# Sheet_MP.net
KiCad netlist of a schematic drawn in Altium Designer
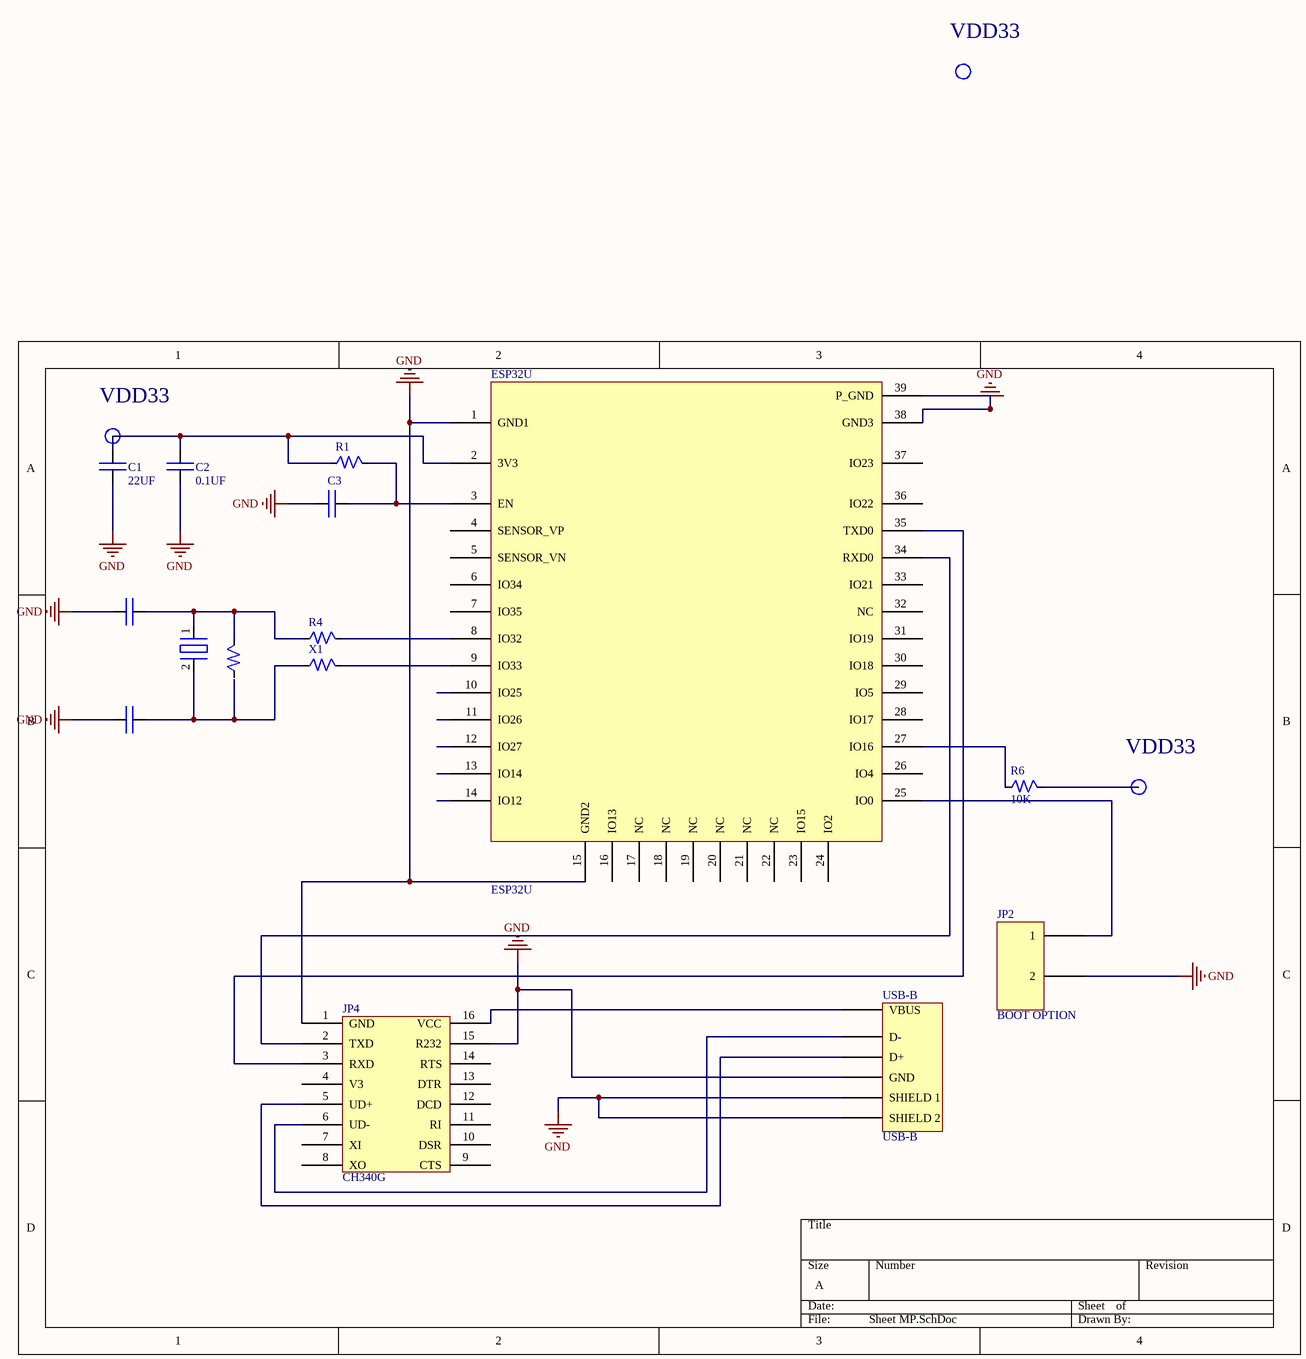
[diagram p0: Sheet MP.SchDoc]

(export (version "E")
  (design (tool "Eeschema 10.0.6"))
  (components
    (comp (ref "C1")
      (value "22UF")
      (footprint "Capacitor")
      (fields (field (name "MANUFACTURER") "PANASONIC") (field (name "MANUFACTURER PART") "EEHZA1V470P"))
      (libsource (lib "SchlibMP") (part "CAP"))
    )
    (comp (ref "C2")
      (value "0.1UF")
      (footprint "Capacitor")
      (fields (field (name "MANUFACTURER") "PANASONIC") (field (name "MANUFACTURER PART") "EEHZA1V470P"))
      (libsource (lib "SchlibMP") (part "CAP"))
    )
    (comp (ref "C3")
      (value "CAP")
      (footprint "Capacitor")
      (fields (field (name "MANUFACTURER") "PANASONIC") (field (name "MANUFACTURER PART") "EEHZA1V470P"))
      (libsource (lib "SchlibMP") (part "CAP"))
    )
    (comp (ref "C4")
      (value "CAP")
      (footprint "Capacitor")
      (fields (field (name "MANUFACTURER") "PANASONIC") (field (name "MANUFACTURER PART") "EEHZA1V470P"))
      (libsource (lib "SchlibMP") (part "CAP"))
    )
    (comp (ref "C5")
      (value "CAP")
      (footprint "Capacitor")
      (fields (field (name "MANUFACTURER") "PANASONIC") (field (name "MANUFACTURER PART") "EEHZA1V470P"))
      (libsource (lib "SchlibMP") (part "CAP"))
    )
    (comp (ref "ESP32U")
      (value "ESP32U")
      (footprint "ESP32U")
      (fields (field (name "MANUFACTURER") "Ai-Thinker") (field (name "MANUFACTURER PART") "ESP32-S"))
      (libsource (lib "SchlibMP") (part "ESP32U"))
    )
    (comp (ref "JP2")
      (value "BOOT OPTION")
      (footprint "HEADER 2 PINS - duplicate")
      (fields
        (field (name "MANUFACTURER") "JST Sales America Inc.")
        (field (name "MANUFACTURER PART") "B2B-XH-A")
      )
      (libsource (lib "SchlibMP") (part "HEADER 2 PINS"))
    )
    (comp (ref "JP4")
      (value "CH340G")
      (footprint "CH340G - duplicate1")
      (fields (field (name "MANUFACTURER") "WCH"))
      (libsource (lib "SchlibMP") (part "CH340G"))
    )
    (comp (ref "R1")
      (value "0805")
      (footprint "Resistor")
      (fields (field (name "MANUFACTURER") "YAGEO") (field (name "MANUFACTURER PART") "RC0805FR-0710KL"))
      (libsource (lib "SchlibMP") (part "0805"))
    )
    (comp (ref "R4")
      (value "0805")
      (footprint "Resistor")
      (fields (field (name "MANUFACTURER") "YAGEO") (field (name "MANUFACTURER PART") "RC0805FR-0710KL"))
      (libsource (lib "SchlibMP") (part "0805"))
    )
    (comp (ref "R5")
      (value "0805")
      (footprint "Resistor")
      (fields (field (name "MANUFACTURER") "YAGEO") (field (name "MANUFACTURER PART") "RC0805FR-0710KL"))
      (libsource (lib "SchlibMP") (part "0805"))
    )
    (comp (ref "R6")
      (value "10K")
      (footprint "Resistor")
      (fields (field (name "MANUFACTURER") "YAGEO") (field (name "MANUFACTURER PART") "RC0805FR-0710KL"))
      (libsource (lib "SchlibMP") (part "0805"))
    )
    (comp (ref "T1")
      (value "CRYSTAL")
      (footprint "CRYSTAL")
      (fields (field (name "MANUFACTURER") "EPSON") (field (name "MANUFACTURER PART") "Q13FC13500004"))
      (libsource (lib "SchlibMP") (part "CRYSTAL"))
    )
    (comp (ref "USB-B")
      (value "USB-B")
      (footprint "USB-B - duplicate1")
      (fields (field (name "MANUFACTURER") "Switchcraft Inc.") (field (name "MANUFACTURER PART") "RAHUB20"))
      (libsource (lib "SchlibMP") (part "USB-B"))
    )
    (comp (ref "X1")
      (value "0805")
      (footprint "Resistor")
      (fields (field (name "MANUFACTURER") "YAGEO") (field (name "MANUFACTURER PART") "RC0805FR-0710KL"))
      (libsource (lib "SchlibMP") (part "0805"))
    )
  )
  (nets
    (net (code "1") (name "GND") (class "Default")
      (node (ref "C1") (pin "1") (pinfunction "1_1") (pintype "passive"))
      (node (ref "C2") (pin "1") (pinfunction "1_1") (pintype "passive"))
      (node (ref "C3") (pin "2") (pinfunction "2_2") (pintype "passive"))
      (node (ref "C4") (pin "2") (pinfunction "2_2") (pintype "passive"))
      (node (ref "C5") (pin "2") (pinfunction "2_2") (pintype "passive"))
      (node (ref "ESP32U") (pin "1") (pinfunction "GND1_1") (pintype "passive"))
      (node (ref "ESP32U") (pin "15") (pinfunction "GND2_15") (pintype "passive"))
      (node (ref "ESP32U") (pin "38") (pinfunction "GND3_38") (pintype "passive"))
      (node (ref "ESP32U") (pin "39") (pinfunction "P_GND_39") (pintype "passive"))
      (node (ref "JP2") (pin "2") (pinfunction "2_2") (pintype "passive"))
      (node (ref "JP4") (pin "1") (pinfunction "GND_1") (pintype "passive"))
      (node (ref "JP4") (pin "15") (pinfunction "R232_15") (pintype "passive"))
      (node (ref "USB-B") (pin "4") (pinfunction "GND_4") (pintype "passive"))
      (node (ref "USB-B") (pin "5") (pinfunction "SHIELD_1_5") (pintype "passive"))
      (node (ref "USB-B") (pin "6") (pinfunction "SHIELD_2_6") (pintype "passive"))
    )
    (net (code "2") (name "Net-(C4-Pad1)") (class "Default")
      (node (ref "C4") (pin "1") (pinfunction "1_1") (pintype "passive"))
      (node (ref "T1") (pin "2") (pinfunction "2_2") (pintype "passive"))
      (node (ref "X1") (pin "1") (pinfunction "1_1") (pintype "passive"))
    )
    (net (code "3") (name "Net-(C5-Pad1)") (class "Default")
      (node (ref "C5") (pin "1") (pinfunction "1_1") (pintype "passive"))
      (node (ref "R4") (pin "1") (pinfunction "1_1") (pintype "passive"))
      (node (ref "R5") (pin "2") (pinfunction "2_2") (pintype "passive"))
      (node (ref "T1") (pin "1") (pinfunction "1_1") (pintype "passive"))
    )
    (net (code "4") (name "Net-(ESP32U-3V3)") (class "Default")
      (node (ref "C1") (pin "2") (pinfunction "2_2") (pintype "passive"))
      (node (ref "C2") (pin "2") (pinfunction "2_2") (pintype "passive"))
      (node (ref "ESP32U") (pin "2") (pinfunction "3V3_2") (pintype "passive"))
      (node (ref "R1") (pin "1") (pinfunction "1_1") (pintype "passive"))
    )
    (net (code "5") (name "Net-(ESP32U-EN)") (class "Default")
      (node (ref "C3") (pin "1") (pinfunction "1_1") (pintype "passive"))
      (node (ref "ESP32U") (pin "3") (pinfunction "EN_3") (pintype "passive"))
      (node (ref "R1") (pin "2") (pinfunction "2_2") (pintype "passive"))
    )
    (net (code "6") (name "Net-(ESP32U-IO0)") (class "Default")
      (node (ref "ESP32U") (pin "25") (pinfunction "IO0_25") (pintype "passive"))
      (node (ref "JP2") (pin "1") (pinfunction "1_1") (pintype "passive"))
    )
    (net (code "7") (name "Net-(ESP32U-IO16)") (class "Default")
      (node (ref "ESP32U") (pin "27") (pinfunction "IO16_27") (pintype "passive"))
      (node (ref "R6") (pin "1") (pinfunction "1_1") (pintype "passive"))
    )
    (net (code "8") (name "Net-(ESP32U-IO32)") (class "Default")
      (node (ref "ESP32U") (pin "8") (pinfunction "IO32_8") (pintype "passive"))
      (node (ref "R4") (pin "2") (pinfunction "2_2") (pintype "passive"))
    )
    (net (code "9") (name "Net-(ESP32U-IO33)") (class "Default")
      (node (ref "ESP32U") (pin "9") (pinfunction "IO33_9") (pintype "passive"))
      (node (ref "X1") (pin "2") (pinfunction "2_2") (pintype "passive"))
    )
    (net (code "10") (name "Net-(ESP32U-RXD0)") (class "Default")
      (node (ref "ESP32U") (pin "34") (pinfunction "RXD0_34") (pintype "passive"))
      (node (ref "JP4") (pin "2") (pinfunction "TXD_2") (pintype "passive"))
    )
    (net (code "11") (name "Net-(ESP32U-TXD0)") (class "Default")
      (node (ref "ESP32U") (pin "35") (pinfunction "TXD0_35") (pintype "passive"))
      (node (ref "JP4") (pin "3") (pinfunction "RXD_3") (pintype "passive"))
    )
    (net (code "12") (name "Net-(JP4-UD+)") (class "Default")
      (node (ref "JP4") (pin "5") (pinfunction "UD+_5") (pintype "passive"))
      (node (ref "USB-B") (pin "3") (pinfunction "D+_3") (pintype "passive"))
    )
    (net (code "13") (name "Net-(JP4-UD-)") (class "Default")
      (node (ref "JP4") (pin "6") (pinfunction "UD-_6") (pintype "passive"))
      (node (ref "USB-B") (pin "2") (pinfunction "D-_2") (pintype "passive"))
    )
    (net (code "14") (name "Net-(JP4-VCC)") (class "Default")
      (node (ref "JP4") (pin "16") (pinfunction "VCC_16") (pintype "passive"))
      (node (ref "USB-B") (pin "1") (pinfunction "VBUS_1") (pintype "passive"))
    )
    (net (code "15") (name "unconnected-(ESP32U-IO2-Pad24)") (class "Default")
      (node (ref "ESP32U") (pin "24") (pinfunction "IO2_24") (pintype "passive"))
    )
    (net (code "16") (name "unconnected-(ESP32U-IO4-Pad26)") (class "Default")
      (node (ref "ESP32U") (pin "26") (pinfunction "IO4_26") (pintype "passive"))
    )
    (net (code "17") (name "unconnected-(ESP32U-IO5-Pad29)") (class "Default")
      (node (ref "ESP32U") (pin "29") (pinfunction "IO5_29") (pintype "passive"))
    )
    (net (code "18") (name "unconnected-(ESP32U-IO12-Pad14)") (class "Default")
      (node (ref "ESP32U") (pin "14") (pinfunction "IO12_14") (pintype "passive"))
    )
    (net (code "19") (name "unconnected-(ESP32U-IO13-Pad16)") (class "Default")
      (node (ref "ESP32U") (pin "16") (pinfunction "IO13_16") (pintype "passive"))
    )
    (net (code "20") (name "unconnected-(ESP32U-IO14-Pad13)") (class "Default")
      (node (ref "ESP32U") (pin "13") (pinfunction "IO14_13") (pintype "passive"))
    )
    (net (code "21") (name "unconnected-(ESP32U-IO15-Pad23)") (class "Default")
      (node (ref "ESP32U") (pin "23") (pinfunction "IO15_23") (pintype "passive"))
    )
    (net (code "22") (name "unconnected-(ESP32U-IO17-Pad28)") (class "Default")
      (node (ref "ESP32U") (pin "28") (pinfunction "IO17_28") (pintype "passive"))
    )
    (net (code "23") (name "unconnected-(ESP32U-IO18-Pad30)") (class "Default")
      (node (ref "ESP32U") (pin "30") (pinfunction "IO18_30") (pintype "passive"))
    )
    (net (code "24") (name "unconnected-(ESP32U-IO19-Pad31)") (class "Default")
      (node (ref "ESP32U") (pin "31") (pinfunction "IO19_31") (pintype "passive"))
    )
    (net (code "25") (name "unconnected-(ESP32U-IO21-Pad33)") (class "Default")
      (node (ref "ESP32U") (pin "33") (pinfunction "IO21_33") (pintype "passive"))
    )
    (net (code "26") (name "unconnected-(ESP32U-IO22-Pad36)") (class "Default")
      (node (ref "ESP32U") (pin "36") (pinfunction "IO22_36") (pintype "passive"))
    )
    (net (code "27") (name "unconnected-(ESP32U-IO23-Pad37)") (class "Default")
      (node (ref "ESP32U") (pin "37") (pinfunction "IO23_37") (pintype "passive"))
    )
    (net (code "28") (name "unconnected-(ESP32U-IO25-Pad10)") (class "Default")
      (node (ref "ESP32U") (pin "10") (pinfunction "IO25_10") (pintype "passive"))
    )
    (net (code "29") (name "unconnected-(ESP32U-IO26-Pad11)") (class "Default")
      (node (ref "ESP32U") (pin "11") (pinfunction "IO26_11") (pintype "passive"))
    )
    (net (code "30") (name "unconnected-(ESP32U-IO27-Pad12)") (class "Default")
      (node (ref "ESP32U") (pin "12") (pinfunction "IO27_12") (pintype "passive"))
    )
    (net (code "31") (name "unconnected-(ESP32U-IO34-Pad6)") (class "Default")
      (node (ref "ESP32U") (pin "6") (pinfunction "IO34_6") (pintype "passive"))
    )
    (net (code "32") (name "unconnected-(ESP32U-IO35-Pad7)") (class "Default")
      (node (ref "ESP32U") (pin "7") (pinfunction "IO35_7") (pintype "passive"))
    )
    (net (code "33") (name "unconnected-(ESP32U-NC-Pad17)") (class "Default")
      (node (ref "ESP32U") (pin "17") (pinfunction "NC_17") (pintype "passive"))
    )
    (net (code "34") (name "unconnected-(ESP32U-NC-Pad18)") (class "Default")
      (node (ref "ESP32U") (pin "18") (pinfunction "NC_18") (pintype "passive"))
    )
    (net (code "35") (name "unconnected-(ESP32U-NC-Pad19)") (class "Default")
      (node (ref "ESP32U") (pin "19") (pinfunction "NC_19") (pintype "passive"))
    )
    (net (code "36") (name "unconnected-(ESP32U-NC-Pad20)") (class "Default")
      (node (ref "ESP32U") (pin "20") (pinfunction "NC_20") (pintype "passive"))
    )
    (net (code "37") (name "unconnected-(ESP32U-NC-Pad21)") (class "Default")
      (node (ref "ESP32U") (pin "21") (pinfunction "NC_21") (pintype "passive"))
    )
    (net (code "38") (name "unconnected-(ESP32U-NC-Pad22)") (class "Default")
      (node (ref "ESP32U") (pin "22") (pinfunction "NC_22") (pintype "passive"))
    )
    (net (code "39") (name "unconnected-(ESP32U-NC-Pad32)") (class "Default")
      (node (ref "ESP32U") (pin "32") (pinfunction "NC_32") (pintype "passive"))
    )
    (net (code "40") (name "unconnected-(ESP32U-SENSOR_VN-Pad5)") (class "Default")
      (node (ref "ESP32U") (pin "5") (pinfunction "SENSOR_VN_5") (pintype "passive"))
    )
    (net (code "41") (name "unconnected-(ESP32U-SENSOR_VP-Pad4)") (class "Default")
      (node (ref "ESP32U") (pin "4") (pinfunction "SENSOR_VP_4") (pintype "passive"))
    )
    (net (code "42") (name "unconnected-(JP4-CTS-Pad9)") (class "Default")
      (node (ref "JP4") (pin "9") (pinfunction "CTS_9") (pintype "passive"))
    )
    (net (code "43") (name "unconnected-(JP4-DCD-Pad12)") (class "Default")
      (node (ref "JP4") (pin "12") (pinfunction "DCD_12") (pintype "passive"))
    )
    (net (code "44") (name "unconnected-(JP4-DSR-Pad10)") (class "Default")
      (node (ref "JP4") (pin "10") (pinfunction "DSR_10") (pintype "passive"))
    )
    (net (code "45") (name "unconnected-(JP4-DTR-Pad13)") (class "Default")
      (node (ref "JP4") (pin "13") (pinfunction "DTR_13") (pintype "passive"))
    )
    (net (code "46") (name "unconnected-(JP4-RI-Pad11)") (class "Default")
      (node (ref "JP4") (pin "11") (pinfunction "RI_11") (pintype "passive"))
    )
    (net (code "47") (name "unconnected-(JP4-RTS-Pad14)") (class "Default")
      (node (ref "JP4") (pin "14") (pinfunction "RTS_14") (pintype "passive"))
    )
    (net (code "48") (name "unconnected-(JP4-V3-Pad4)") (class "Default")
      (node (ref "JP4") (pin "4") (pinfunction "V3_4") (pintype "passive"))
    )
    (net (code "49") (name "unconnected-(JP4-XI-Pad7)") (class "Default")
      (node (ref "JP4") (pin "7") (pinfunction "XI_7") (pintype "passive"))
    )
    (net (code "50") (name "unconnected-(JP4-XO-Pad8)") (class "Default")
      (node (ref "JP4") (pin "8") (pinfunction "XO_8") (pintype "passive"))
    )
    (net (code "51") (name "unconnected-(R5-Pad1)") (class "Default")
      (node (ref "R5") (pin "1") (pinfunction "1_1") (pintype "passive"))
    )
    (net (code "52") (name "unconnected-(R6-Pad2)") (class "Default")
      (node (ref "R6") (pin "2") (pinfunction "2_2") (pintype "passive"))
    )
  )
)
